# 34_PP1_JTAG_PCIe.net
KiCad netlist of a schematic drawn in Altium Designer
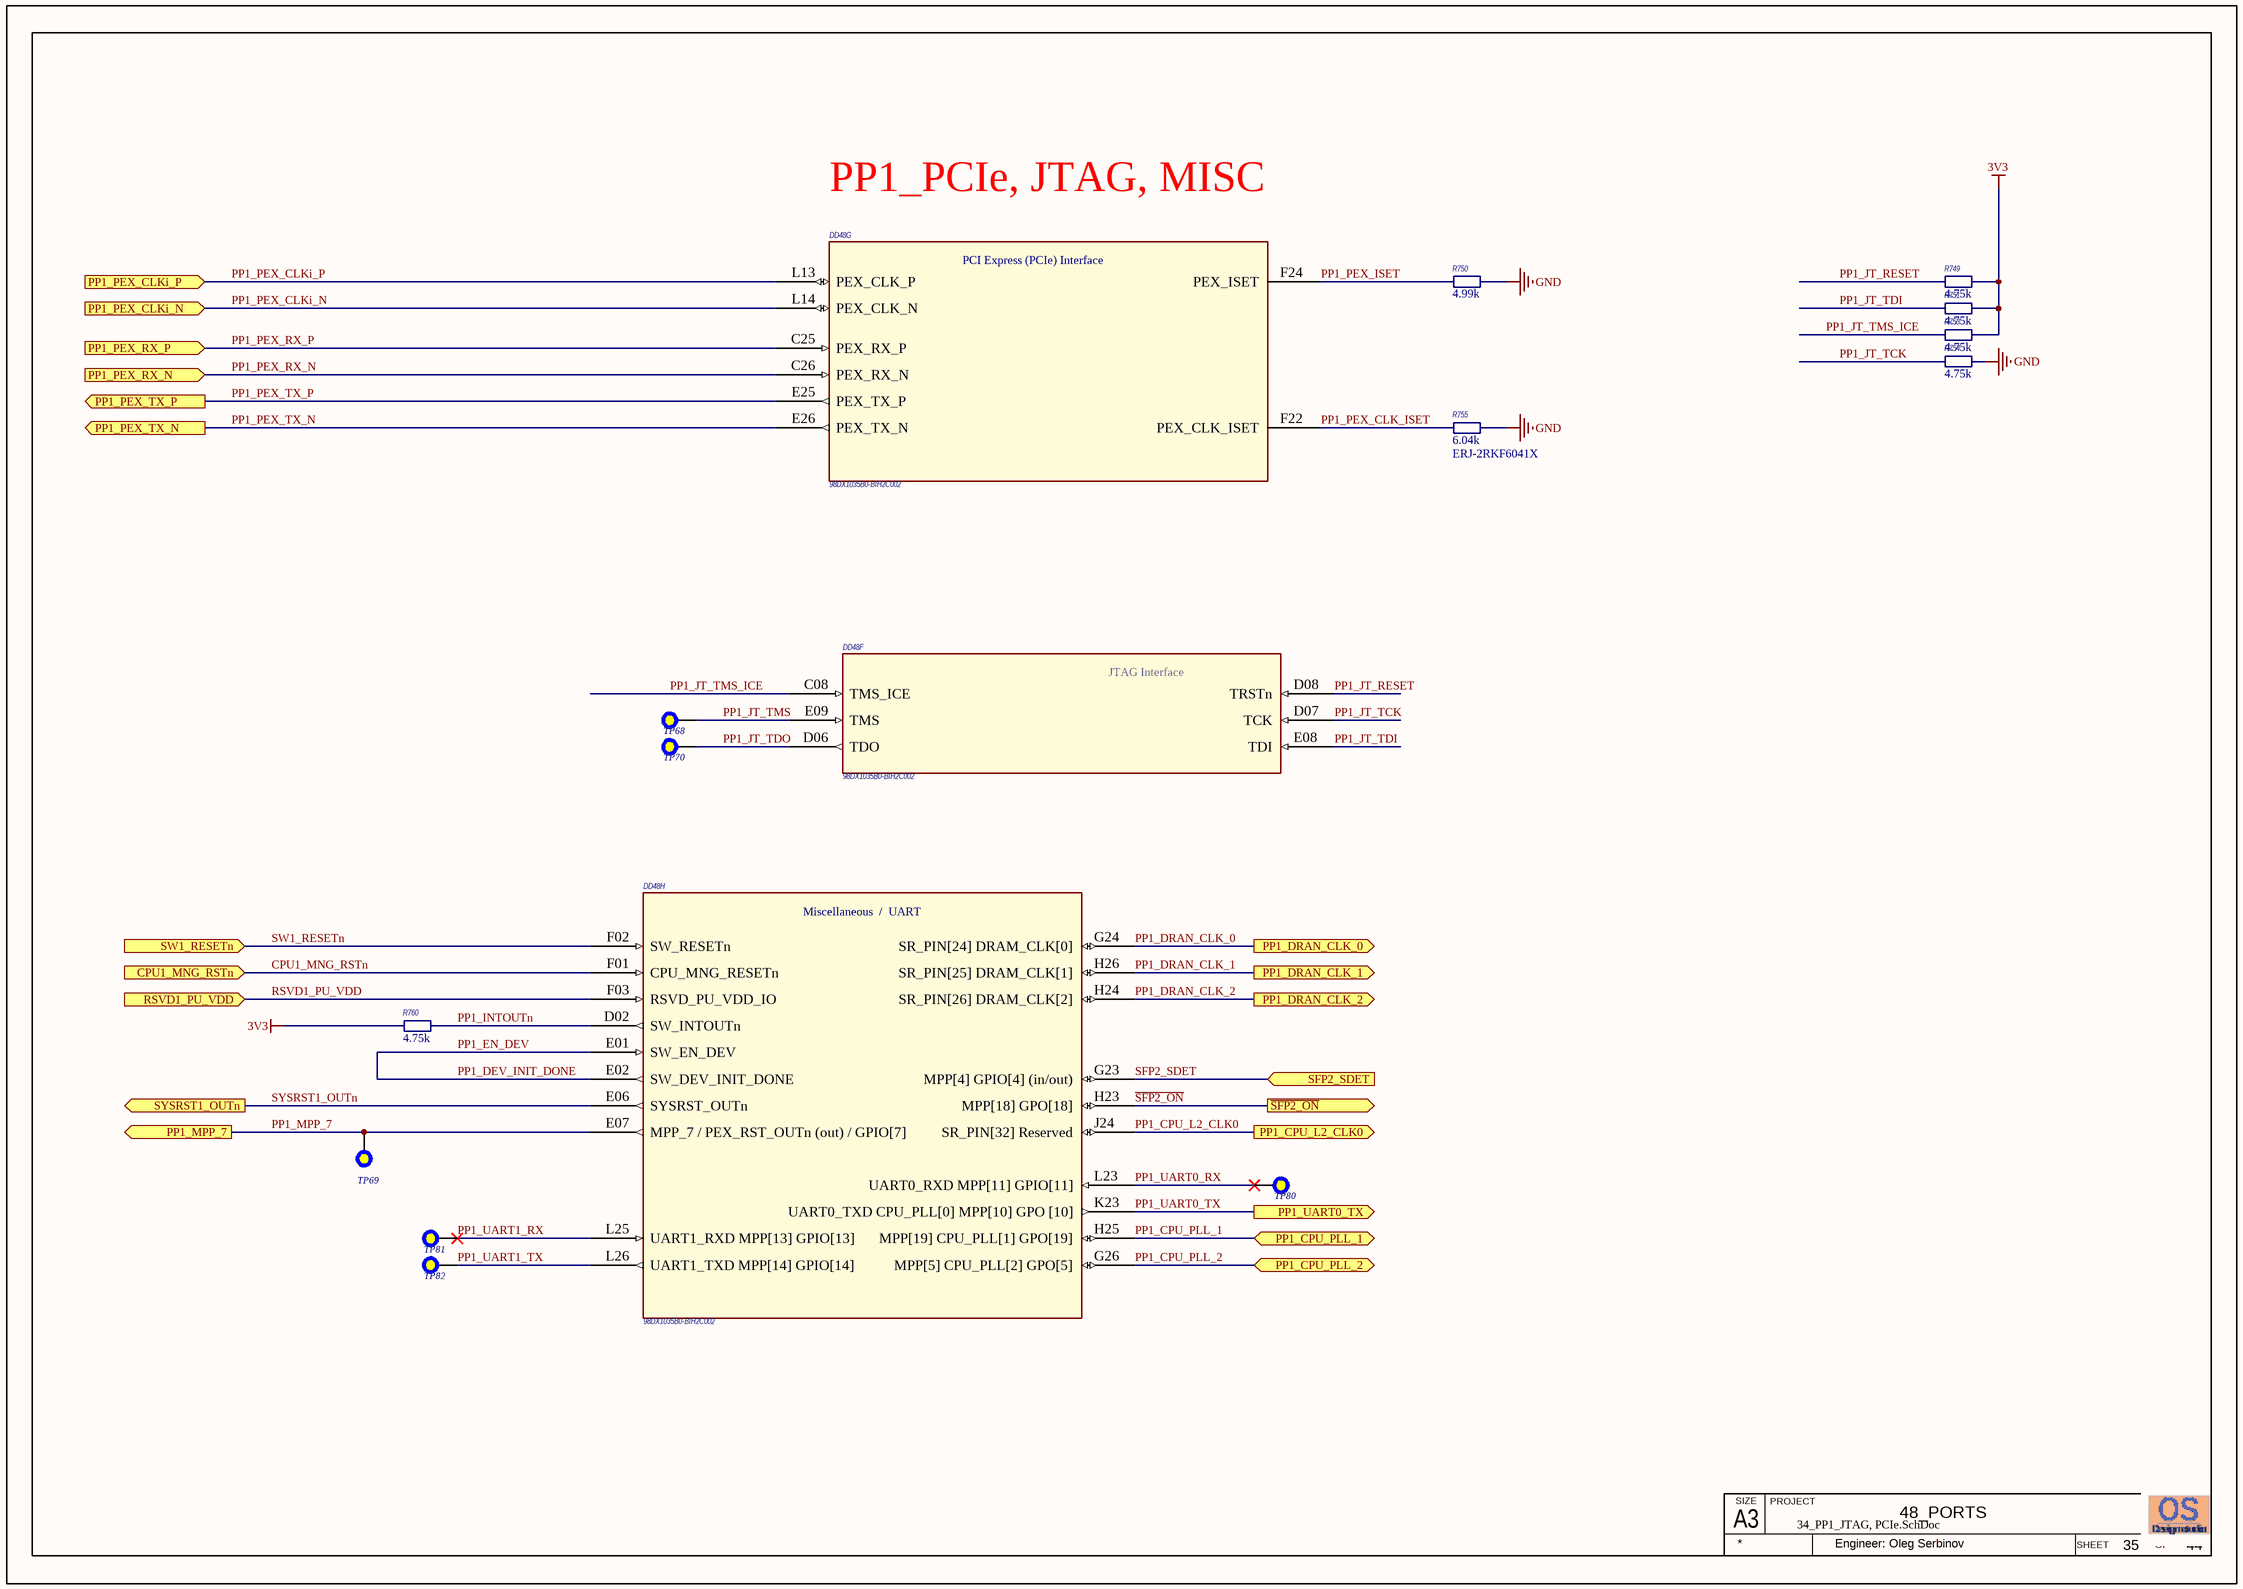
[diagram p0: 34_PP1_JTAG, PCIe.SchDoc]

(export (version "E")
  (design (tool "Eeschema 10.0.6"))
  (components
    (comp (ref "DD48")
      (value "98DX1035B0-BIH2C002")
      (footprint "HSBGA617_27X27_1MM")
      (description "IC 24-PORT FE  4-PORT 2.5GE L2 ENTRY-LEVEL, CPU")
      (fields
        (field (name "CUSTOMER PART NUMBER") "Микросхема, 98DX1035B0-BIH2C002, IC 24-PORT FE 4-PORT 2.5GE L2 ENTRY-LEVEL, HSBGA617SBGA617")
        (field (name "MANUFACTURER") "Marvell Technology Group")
      )
      (libsource (lib "") (part "98DX1035A1-BIH2C002_1"))
    )
    (comp (ref "R749")
      (value "ERJ-2RKF4751X")
      (footprint "R0402_IPC High Density")
      (description "R0402, 4.75k 1%")
      (fields
        (field (name "TOLERANCE") "±1%")
        (field (name "MANUFACTURER") "Panasonic")
        (field (name "RESISTANCE (OHMS)") "4.75k")
      )
      (libsource (lib "RESISTOR") (part "ERJ-2RKF4751X"))
    )
    (comp (ref "R750")
      (value "ERJ-2RKF4991X")
      (footprint "R0402_IPC High Density")
      (description "R0402, 4.99k 1%")
      (fields
        (field (name "TOLERANCE") "±1%")
        (field (name "MANUFACTURER") "Panasonic")
        (field (name "RESISTANCE (OHMS)") "4.99k")
      )
      (libsource (lib "RESISTOR") (part "ERJ-2RKF4991X"))
    )
    (comp (ref "R751")
      (value "ERJ-2RKF4751X")
      (footprint "R0402_IPC High Density")
      (description "R0402, 4.75k 1%")
      (fields
        (field (name "TOLERANCE") "±1%")
        (field (name "MANUFACTURER") "Panasonic")
        (field (name "RESISTANCE (OHMS)") "4.75k")
      )
      (libsource (lib "RESISTOR") (part "ERJ-2RKF4751X"))
    )
    (comp (ref "R753")
      (value "ERJ-2RKF4751X")
      (footprint "R0402_IPC High Density")
      (description "R0402, 4.75k 1%")
      (fields
        (field (name "TOLERANCE") "±1%")
        (field (name "MANUFACTURER") "Panasonic")
        (field (name "RESISTANCE (OHMS)") "4.75k")
      )
      (libsource (lib "RESISTOR") (part "ERJ-2RKF4751X"))
    )
    (comp (ref "R754")
      (value "ERJ-2RKF4751X")
      (footprint "R0402_IPC High Density")
      (description "R0402, 4.75k 1%")
      (fields
        (field (name "TOLERANCE") "±1%")
        (field (name "MANUFACTURER") "Panasonic")
        (field (name "RESISTANCE (OHMS)") "4.75k")
      )
      (libsource (lib "RESISTOR") (part "ERJ-2RKF4751X"))
    )
    (comp (ref "R755")
      (value "ERJ-2RKF6041X")
      (footprint "R0402_IPC High Density")
      (description "R0402, 6.04k 1%")
      (fields
        (field (name "TOLERANCE") "±1%")
        (field (name "MANUFACTURER") "Panasonic")
        (field (name "RESISTANCE (OHMS)") "6.04k")
        (field (name "MANUFACTURER PART NUMBER") "ERJ-2RKF6041X")
      )
      (libsource (lib "RESISTOR") (part "ERJ-2RKF6041X"))
    )
    (comp (ref "R760")
      (value "ERJ-2RKF4751X")
      (footprint "R0402_IPC High Density")
      (description "R0402, 4.75k 1%")
      (fields
        (field (name "TOLERANCE") "±1%")
        (field (name "MANUFACTURER") "Panasonic")
        (field (name "RESISTANCE (OHMS)") "4.75k")
      )
      (libsource (lib "RESISTOR") (part "ERJ-2RKF4751X"))
    )
    (comp (ref "TP68")
      (value "Test Point 0.5mm pad")
      (footprint "Test Point 0.5mm")
      (libsource (lib "CONNECTORS") (part "Test Point 0.5mm pad"))
    )
    (comp (ref "TP69")
      (value "Test Point 0.5mm pad")
      (footprint "Test Point 0.5mm")
      (libsource (lib "CONNECTORS") (part "Test Point 0.5mm pad"))
    )
    (comp (ref "TP70")
      (value "Test Point 0.5mm pad")
      (footprint "Test Point 0.5mm")
      (libsource (lib "CONNECTORS") (part "Test Point 0.5mm pad"))
    )
    (comp (ref "TP80")
      (value "Test Point 0.5mm pad")
      (footprint "Test Point 0.5mm")
      (libsource (lib "CONNECTORS") (part "Test Point 0.5mm pad"))
    )
    (comp (ref "TP81")
      (value "Test Point 0.5mm pad")
      (footprint "Test Point 0.5mm")
      (libsource (lib "CONNECTORS") (part "Test Point 0.5mm pad"))
    )
    (comp (ref "TP82")
      (value "Test Point 0.5mm pad")
      (footprint "Test Point 0.5mm")
      (libsource (lib "CONNECTORS") (part "Test Point 0.5mm pad"))
    )
  )
  (nets
    (net (code "1") (name "/CPU1_MNG_RSTn") (class "Default")
      (node (ref "DD48") (pin "F01") (pinfunction "CPU_MNG_RESETn_F01") (pintype "input"))
    )
    (net (code "2") (name "/PP1_CPU_L2_CLK0") (class "Default")
      (node (ref "DD48") (pin "J24") (pinfunction "SR_PIN[32]_Reserved_J24") (pintype "bidirectional"))
    )
    (net (code "3") (name "/PP1_CPU_PLL_1") (class "Default")
      (node (ref "DD48") (pin "H25") (pinfunction "MPP[19]_CPU_PLL[1]_GPO[19]_H25") (pintype "bidirectional"))
    )
    (net (code "4") (name "/PP1_CPU_PLL_2") (class "Default")
      (node (ref "DD48") (pin "G26") (pinfunction "MPP[5]_CPU_PLL[2]_GPO[5]_G26") (pintype "bidirectional"))
    )
    (net (code "5") (name "/PP1_DEV_INIT_DONE") (class "Default")
      (node (ref "DD48") (pin "E01") (pinfunction "SW_EN_DEV_E01") (pintype "input"))
      (node (ref "DD48") (pin "E02") (pinfunction "SW_DEV_INIT_DONE_E02") (pintype "output"))
    )
    (net (code "6") (name "/PP1_DRAN_CLK_0") (class "Default")
      (node (ref "DD48") (pin "G24") (pinfunction "SR_PIN[24]_DRAM_CLK[0]_G24") (pintype "bidirectional"))
    )
    (net (code "7") (name "/PP1_DRAN_CLK_1") (class "Default")
      (node (ref "DD48") (pin "H26") (pinfunction "SR_PIN[25]_DRAM_CLK[1]_H26") (pintype "bidirectional"))
    )
    (net (code "8") (name "/PP1_DRAN_CLK_2") (class "Default")
      (node (ref "DD48") (pin "H24") (pinfunction "SR_PIN[26]_DRAM_CLK[2]_H24") (pintype "bidirectional"))
    )
    (net (code "9") (name "/PP1_INTOUTn") (class "Default")
      (node (ref "DD48") (pin "D02") (pinfunction "SW_INTOUTn_D02") (pintype "output"))
      (node (ref "R760") (pin "2") (pintype "passive"))
    )
    (net (code "10") (name "/PP1_JT_RESET") (class "Default")
      (node (ref "DD48") (pin "D08") (pinfunction "TRSTn_D08") (pintype "input"))
      (node (ref "R749") (pin "1") (pintype "passive"))
    )
    (net (code "11") (name "/PP1_JT_TCK") (class "Default")
      (node (ref "DD48") (pin "D07") (pinfunction "TCK_D07") (pintype "input"))
      (node (ref "R754") (pin "1") (pintype "passive"))
    )
    (net (code "12") (name "/PP1_JT_TDI") (class "Default")
      (node (ref "DD48") (pin "E08") (pinfunction "TDI_E08") (pintype "input"))
      (node (ref "R751") (pin "1") (pintype "passive"))
    )
    (net (code "13") (name "/PP1_JT_TDO") (class "Default")
      (node (ref "DD48") (pin "D06") (pinfunction "TDO_D06") (pintype "output"))
      (node (ref "TP70") (pin "1") (pinfunction "1_1") (pintype "passive"))
    )
    (net (code "14") (name "/PP1_JT_TMS") (class "Default")
      (node (ref "DD48") (pin "E09") (pinfunction "TMS_E09") (pintype "input"))
      (node (ref "TP68") (pin "1") (pinfunction "1_1") (pintype "passive"))
    )
    (net (code "15") (name "/PP1_JT_TMS_ICE") (class "Default")
      (node (ref "DD48") (pin "C08") (pinfunction "TMS_ICE_C08") (pintype "input"))
      (node (ref "R753") (pin "1") (pintype "passive"))
    )
    (net (code "16") (name "/PP1_MPP_7") (class "Default")
      (node (ref "DD48") (pin "E07") (pinfunction "MPP_7_/_PEX_RST_OUTn_(out)_/_GPIO[7]_E07") (pintype "output"))
      (node (ref "TP69") (pin "1") (pinfunction "1_1") (pintype "passive"))
    )
    (net (code "17") (name "/PP1_PEX_CLK_ISET") (class "Default")
      (node (ref "DD48") (pin "F22") (pinfunction "PEX_CLK_ISET_F22") (pintype "power_in"))
      (node (ref "R755") (pin "1") (pintype "passive"))
    )
    (net (code "18") (name "/PP1_PEX_CLKi_N") (class "Default")
      (node (ref "DD48") (pin "L14") (pinfunction "PEX_CLK_N_L14") (pintype "bidirectional"))
    )
    (net (code "19") (name "/PP1_PEX_CLKi_P") (class "Default")
      (node (ref "DD48") (pin "L13") (pinfunction "PEX_CLK_P_L13") (pintype "bidirectional"))
    )
    (net (code "20") (name "/PP1_PEX_ISET") (class "Default")
      (node (ref "DD48") (pin "F24") (pinfunction "PEX_ISET_F24") (pintype "power_in"))
      (node (ref "R750") (pin "1") (pintype "passive"))
    )
    (net (code "21") (name "/PP1_PEX_RX_N") (class "Default")
      (node (ref "DD48") (pin "C26") (pinfunction "PEX_RX_N_C26") (pintype "input"))
    )
    (net (code "22") (name "/PP1_PEX_RX_P") (class "Default")
      (node (ref "DD48") (pin "C25") (pinfunction "PEX_RX_P_C25") (pintype "input"))
    )
    (net (code "23") (name "/PP1_PEX_TX_N") (class "Default")
      (node (ref "DD48") (pin "E26") (pinfunction "PEX_TX_N_E26") (pintype "output"))
    )
    (net (code "24") (name "/PP1_PEX_TX_P") (class "Default")
      (node (ref "DD48") (pin "E25") (pinfunction "PEX_TX_P_E25") (pintype "output"))
    )
    (net (code "25") (name "/PP1_UART0_RX") (class "Default")
      (node (ref "DD48") (pin "L23") (pinfunction "UART0_RXD_MPP[11]_GPIO[11]_L23") (pintype "input"))
      (node (ref "TP80") (pin "1") (pinfunction "1_1") (pintype "passive"))
    )
    (net (code "26") (name "/PP1_UART0_TX") (class "Default")
      (node (ref "DD48") (pin "K23") (pinfunction "UART0_TXD_CPU_PLL[0]_MPP[10]_GPO_[10]_K23") (pintype "output"))
    )
    (net (code "27") (name "/PP1_UART1_RX") (class "Default")
      (node (ref "DD48") (pin "L25") (pinfunction "UART1_RXD_MPP[13]_GPIO[13]_L25") (pintype "input"))
      (node (ref "TP81") (pin "1") (pinfunction "1_1") (pintype "passive"))
    )
    (net (code "28") (name "/PP1_UART1_TX") (class "Default")
      (node (ref "DD48") (pin "L26") (pinfunction "UART1_TXD_MPP[14]_GPIO[14]_L26") (pintype "output"))
      (node (ref "TP82") (pin "1") (pinfunction "1_1") (pintype "passive"))
    )
    (net (code "29") (name "/RSVD1_PU_VDD") (class "Default")
      (node (ref "DD48") (pin "F03") (pinfunction "RSVD_PU_VDD_IO_F03") (pintype "input"))
    )
    (net (code "30") (name "/SFP2_ON") (class "Default")
      (node (ref "DD48") (pin "H23") (pinfunction "MPP[18]_GPO[18]_H23") (pintype "bidirectional"))
    )
    (net (code "31") (name "/SFP2_SDET") (class "Default")
      (node (ref "DD48") (pin "G23") (pinfunction "MPP[4]_GPIO[4]_(in/out)_G23") (pintype "bidirectional"))
    )
    (net (code "32") (name "/SW1_RESETn") (class "Default")
      (node (ref "DD48") (pin "F02") (pinfunction "SW_RESETn_F02") (pintype "input"))
    )
    (net (code "33") (name "/SYSRST1_OUTn") (class "Default")
      (node (ref "DD48") (pin "E06") (pinfunction "SYSRST_OUTn_E06") (pintype "output"))
    )
    (net (code "34") (name "3V3") (class "Default")
      (node (ref "R749") (pin "2") (pintype "passive"))
      (node (ref "R751") (pin "2") (pintype "passive"))
      (node (ref "R753") (pin "2") (pintype "passive"))
      (node (ref "R760") (pin "1") (pintype "passive"))
    )
    (net (code "35") (name "GND") (class "Default")
      (node (ref "R750") (pin "2") (pintype "passive"))
      (node (ref "R754") (pin "2") (pintype "passive"))
      (node (ref "R755") (pin "2") (pintype "passive"))
    )
  )
)
